# Channel_4.net
KiCad netlist of a schematic drawn in Altium Designer
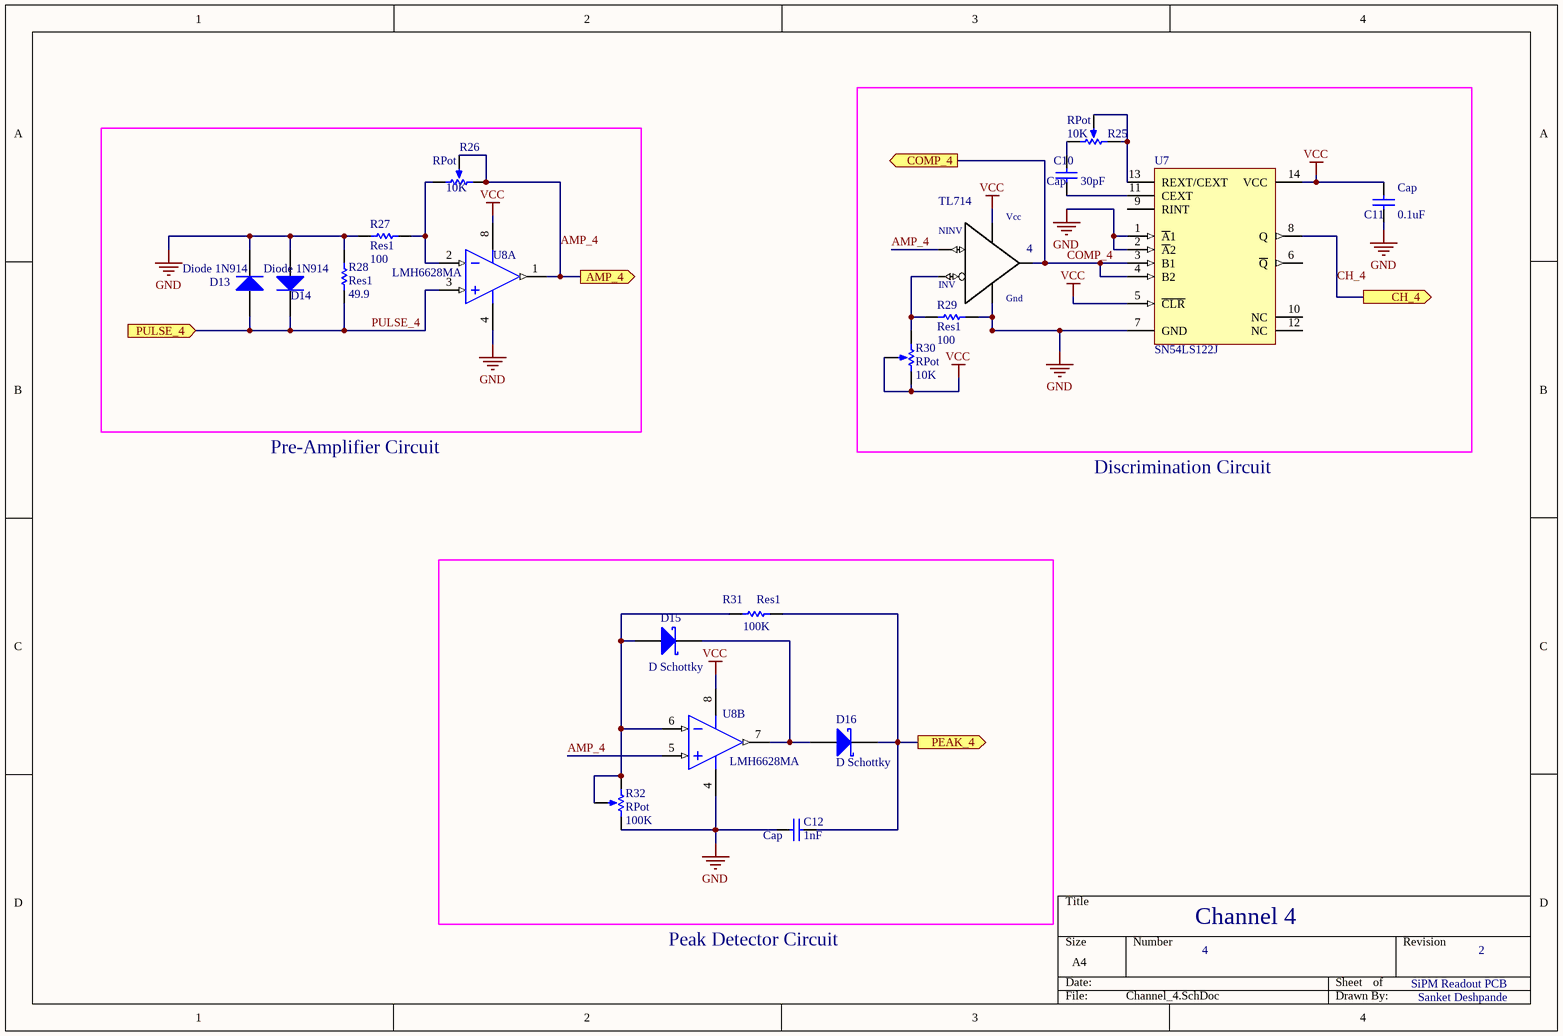
[diagram p0: Channel_4.SchDoc]

(export (version "E")
  (design (tool "Eeschema 10.0.6"))
  (components
    (comp (ref "4")
      (value "TL714")
      (footprint "SO-08M")
      (fields (field (name "MF") "Texas Instruments"))
      (libsource (lib "TL714") (part "TL714"))
    )
    (comp (ref "C10")
      (value "Cap")
      (footprint "RAD-0.3")
      (description "Capacitor")
      (fields (field (name "ALTIUM_VALUE") "30pF") (field (name "PUBLISHER") "Altium Limited"))
      (libsource (lib "Miscellaneous Devices") (part "Cap"))
    )
    (comp (ref "C11")
      (value "Cap")
      (footprint "RAD-0.3")
      (description "Capacitor")
      (fields (field (name "ALTIUM_VALUE") "0.1uF") (field (name "PUBLISHER") "Altium Limited"))
      (libsource (lib "Miscellaneous Devices") (part "Cap"))
    )
    (comp (ref "C12")
      (value "Cap")
      (footprint "RAD-0.3")
      (description "Capacitor")
      (fields (field (name "ALTIUM_VALUE") "1nF") (field (name "PUBLISHER") "Altium Limited"))
      (libsource (lib "Miscellaneous Devices") (part "Cap"))
    )
    (comp (ref "D13")
      (value "Diode 1N914")
      (footprint "DO-35")
      (description "High Conductance Fast Diode")
      (fields (field (name "PUBLISHER") "Altium Limited"))
      (libsource (lib "Miscellaneous Devices") (part "Diode 1N914"))
    )
    (comp (ref "D14")
      (value "Diode 1N914")
      (footprint "DO-35")
      (description "High Conductance Fast Diode")
      (fields (field (name "PUBLISHER") "Altium Limited"))
      (libsource (lib "Miscellaneous Devices") (part "Diode 1N914"))
    )
    (comp (ref "D15")
      (value "D Schottky")
      (footprint "SMB")
      (description "Schottky Diode")
      (fields (field (name "PUBLISHER") "Altium Limited"))
      (libsource (lib "Miscellaneous Devices") (part "D Schottky"))
    )
    (comp (ref "D16")
      (value "D Schottky")
      (footprint "SMB")
      (description "Schottky Diode")
      (fields (field (name "PUBLISHER") "Altium Limited"))
      (libsource (lib "Miscellaneous Devices") (part "D Schottky"))
    )
    (comp (ref "R25")
      (value "RPot")
      (footprint "VR5")
      (description "Potentiometer")
      (fields (field (name "ALTIUM_VALUE") "10K") (field (name "PUBLISHER") "Altium Limited"))
      (libsource (lib "Miscellaneous Devices") (part "RPot"))
    )
    (comp (ref "R26")
      (value "RPot")
      (footprint "VR5")
      (description "Potentiometer")
      (fields (field (name "ALTIUM_VALUE") "10K") (field (name "PUBLISHER") "Altium Limited"))
      (libsource (lib "Miscellaneous Devices") (part "RPot"))
    )
    (comp (ref "R27")
      (value "Res1")
      (footprint "AXIAL-0.3")
      (description "Resistor")
      (fields (field (name "ALTIUM_VALUE") "100") (field (name "PUBLISHER") "Altium Limited"))
      (libsource (lib "Miscellaneous Devices") (part "Res1"))
    )
    (comp (ref "R28")
      (value "Res1")
      (footprint "AXIAL-0.3")
      (description "Resistor")
      (fields (field (name "ALTIUM_VALUE") "49.9") (field (name "PUBLISHER") "Altium Limited"))
      (libsource (lib "Miscellaneous Devices") (part "Res1"))
    )
    (comp (ref "R29")
      (value "Res1")
      (footprint "AXIAL-0.3")
      (description "Resistor")
      (fields (field (name "ALTIUM_VALUE") "100") (field (name "PUBLISHER") "Altium Limited"))
      (libsource (lib "Miscellaneous Devices") (part "Res1"))
    )
    (comp (ref "R30")
      (value "RPot")
      (footprint "VR5")
      (description "Potentiometer")
      (fields (field (name "ALTIUM_VALUE") "10K") (field (name "PUBLISHER") "Altium Limited"))
      (libsource (lib "Miscellaneous Devices") (part "RPot"))
    )
    (comp (ref "R31")
      (value "Res1")
      (footprint "AXIAL-0.3")
      (description "Resistor")
      (fields (field (name "ALTIUM_VALUE") "100K") (field (name "PUBLISHER") "Altium Limited"))
      (libsource (lib "Miscellaneous Devices") (part "Res1"))
    )
    (comp (ref "R32")
      (value "RPot")
      (footprint "VR5")
      (description "Potentiometer")
      (fields (field (name "ALTIUM_VALUE") "100K") (field (name "PUBLISHER") "Altium Limited"))
      (libsource (lib "Miscellaneous Devices") (part "RPot"))
    )
    (comp (ref "U7")
      (value "SN54LS122J")
      (footprint "J014")
      (description "Retriggerable Monostable Multivibrator")
      (fields (field (name "PUBLISHER") "Altium Limited"))
      (libsource (lib "TI Logic Multivibrator") (part "SN54LS122J"))
    )
    (comp (ref "U8")
      (value "LMH6628MA")
      (footprint "M08A_N")
      (description "Dual Wideband, Low Noise, Voltage Feedback Op Amp, 8-pin Narrow SOIC")
      (fields (field (name "MANUFACTURER") "National Semiconductor"))
      (libsource (lib "National Semiconductor Amplifier") (part "LMH6628MA"))
    )
  )
  (nets
    (net (code "1") (name "/AMP_4") (class "Default")
      (node (ref "4") (pin "3") (pinfunction "NINV_3") (pintype "bidirectional"))
      (node (ref "R26") (pin "1") (pinfunction "TOP_1") (pintype "passive"))
      (node (ref "R26") (pin "3") (pinfunction "TAP_3") (pintype "passive"))
      (node (ref "U8") (pin "1") (pinfunction "OUT1_1") (pintype "output"))
      (node (ref "U8") (pin "5") (pinfunction "IN2+_5") (pintype "input"))
    )
    (net (code "2") (name "/CH_4") (class "Default")
      (node (ref "U7") (pin "8") (pinfunction "Q_8") (pintype "output"))
    )
    (net (code "3") (name "/COMP_4") (class "Default")
      (node (ref "4") (pin "6") (pinfunction "OUT_6") (pintype "bidirectional"))
      (node (ref "U7") (pin "3") (pinfunction "B1_3") (pintype "input"))
      (node (ref "U7") (pin "4") (pinfunction "B2_4") (pintype "input"))
    )
    (net (code "4") (name "/PEAK_4") (class "Default")
      (node (ref "C12") (pin "2") (pinfunction "2_2") (pintype "passive"))
      (node (ref "D16") (pin "2") (pinfunction "K_2") (pintype "passive"))
      (node (ref "R31") (pin "2") (pinfunction "2_2") (pintype "passive"))
    )
    (net (code "5") (name "/PULSE_4") (class "Default")
      (node (ref "D13") (pin "1") (pinfunction "A_1") (pintype "passive"))
      (node (ref "D14") (pin "2") (pinfunction "K_2") (pintype "passive"))
      (node (ref "R28") (pin "2") (pinfunction "2_2") (pintype "passive"))
      (node (ref "U8") (pin "3") (pinfunction "IN1+_3") (pintype "input"))
    )
    (net (code "6") (name "GND") (class "Default")
      (node (ref "4") (pin "5") (pinfunction "VNEG_5") (pintype "bidirectional"))
      (node (ref "C11") (pin "1") (pinfunction "1_1") (pintype "passive"))
      (node (ref "C12") (pin "1") (pinfunction "1_1") (pintype "passive"))
      (node (ref "D13") (pin "2") (pinfunction "K_2") (pintype "passive"))
      (node (ref "D14") (pin "1") (pinfunction "A_1") (pintype "passive"))
      (node (ref "R27") (pin "1") (pinfunction "1_1") (pintype "passive"))
      (node (ref "R28") (pin "1") (pinfunction "1_1") (pintype "passive"))
      (node (ref "R29") (pin "2") (pinfunction "2_2") (pintype "passive"))
      (node (ref "R32") (pin "2") (pinfunction "BOT_2") (pintype "passive"))
      (node (ref "U7") (pin "1") (pinfunction "~{A}1_1") (pintype "input"))
      (node (ref "U7") (pin "2") (pinfunction "~{A}2_2") (pintype "input"))
      (node (ref "U7") (pin "7") (pinfunction "GND_7") (pintype "power_in"))
      (node (ref "U8") (pin "4") (pinfunction "V-_4") (pintype "power_in"))
    )
    (net (code "7") (name "Net-(4-INV)") (class "Default")
      (node (ref "4") (pin "2") (pinfunction "INV_2") (pintype "bidirectional"))
      (node (ref "R29") (pin "1") (pinfunction "1_1") (pintype "passive"))
      (node (ref "R30") (pin "1") (pinfunction "TOP_1") (pintype "passive"))
    )
    (net (code "8") (name "Net-(D15-A)") (class "Default")
      (node (ref "D15") (pin "1") (pinfunction "A_1") (pintype "passive"))
      (node (ref "R31") (pin "1") (pinfunction "1_1") (pintype "passive"))
      (node (ref "R32") (pin "1") (pinfunction "TOP_1") (pintype "passive"))
      (node (ref "R32") (pin "3") (pinfunction "TAP_3") (pintype "passive"))
      (node (ref "U8") (pin "6") (pinfunction "IN2-_6") (pintype "input"))
    )
    (net (code "9") (name "Net-(D15-K)") (class "Default")
      (node (ref "D15") (pin "2") (pinfunction "K_2") (pintype "passive"))
      (node (ref "D16") (pin "1") (pinfunction "A_1") (pintype "passive"))
      (node (ref "U8") (pin "7") (pinfunction "OUT2_7") (pintype "output"))
    )
    (net (code "10") (name "Net-(R25-BOT)") (class "Default")
      (node (ref "C10") (pin "2") (pinfunction "2_2") (pintype "passive"))
      (node (ref "R25") (pin "2") (pinfunction "BOT_2") (pintype "passive"))
    )
    (net (code "11") (name "Net-(R25-TAP)") (class "Default")
      (node (ref "R25") (pin "1") (pinfunction "TOP_1") (pintype "passive"))
      (node (ref "R25") (pin "3") (pinfunction "TAP_3") (pintype "passive"))
      (node (ref "U7") (pin "13") (pinfunction "REXT/CEXT_13") (pintype "passive"))
    )
    (net (code "12") (name "Net-(R26-BOT)") (class "Default")
      (node (ref "R26") (pin "2") (pinfunction "BOT_2") (pintype "passive"))
      (node (ref "R27") (pin "2") (pinfunction "2_2") (pintype "passive"))
      (node (ref "U8") (pin "2") (pinfunction "IN1-_2") (pintype "input"))
    )
    (net (code "13") (name "Net-(U7-CEXT)") (class "Default")
      (node (ref "C10") (pin "1") (pinfunction "1_1") (pintype "passive"))
      (node (ref "U7") (pin "11") (pinfunction "CEXT_11") (pintype "passive"))
    )
    (net (code "14") (name "VCC") (class "Default")
      (node (ref "4") (pin "8") (pinfunction "VPOS_8") (pintype "bidirectional"))
      (node (ref "C11") (pin "2") (pinfunction "2_2") (pintype "passive"))
      (node (ref "R30") (pin "2") (pinfunction "BOT_2") (pintype "passive"))
      (node (ref "R30") (pin "3") (pinfunction "TAP_3") (pintype "passive"))
      (node (ref "U7") (pin "14") (pinfunction "VCC_14") (pintype "power_in"))
      (node (ref "U7") (pin "5") (pinfunction "~{CLR}_5") (pintype "input"))
      (node (ref "U8") (pin "8") (pinfunction "V+_8") (pintype "power_in"))
    )
    (net (code "15") (name "unconnected-(U7-NC-Pad10)") (class "Default")
      (node (ref "U7") (pin "10") (pinfunction "NC_10") (pintype "passive"))
    )
    (net (code "16") (name "unconnected-(U7-NC-Pad12)") (class "Default")
      (node (ref "U7") (pin "12") (pinfunction "NC_12") (pintype "passive"))
    )
    (net (code "17") (name "unconnected-(U7-RINT-Pad9)") (class "Default")
      (node (ref "U7") (pin "9") (pinfunction "RINT_9") (pintype "passive"))
    )
    (net (code "18") (name "unconnected-(U7-~{Q}-Pad6)") (class "Default")
      (node (ref "U7") (pin "6") (pinfunction "~{Q}_6") (pintype "output"))
    )
  )
)
